# STM32F417_module.net
KiCad netlist of a schematic drawn in EAGLE
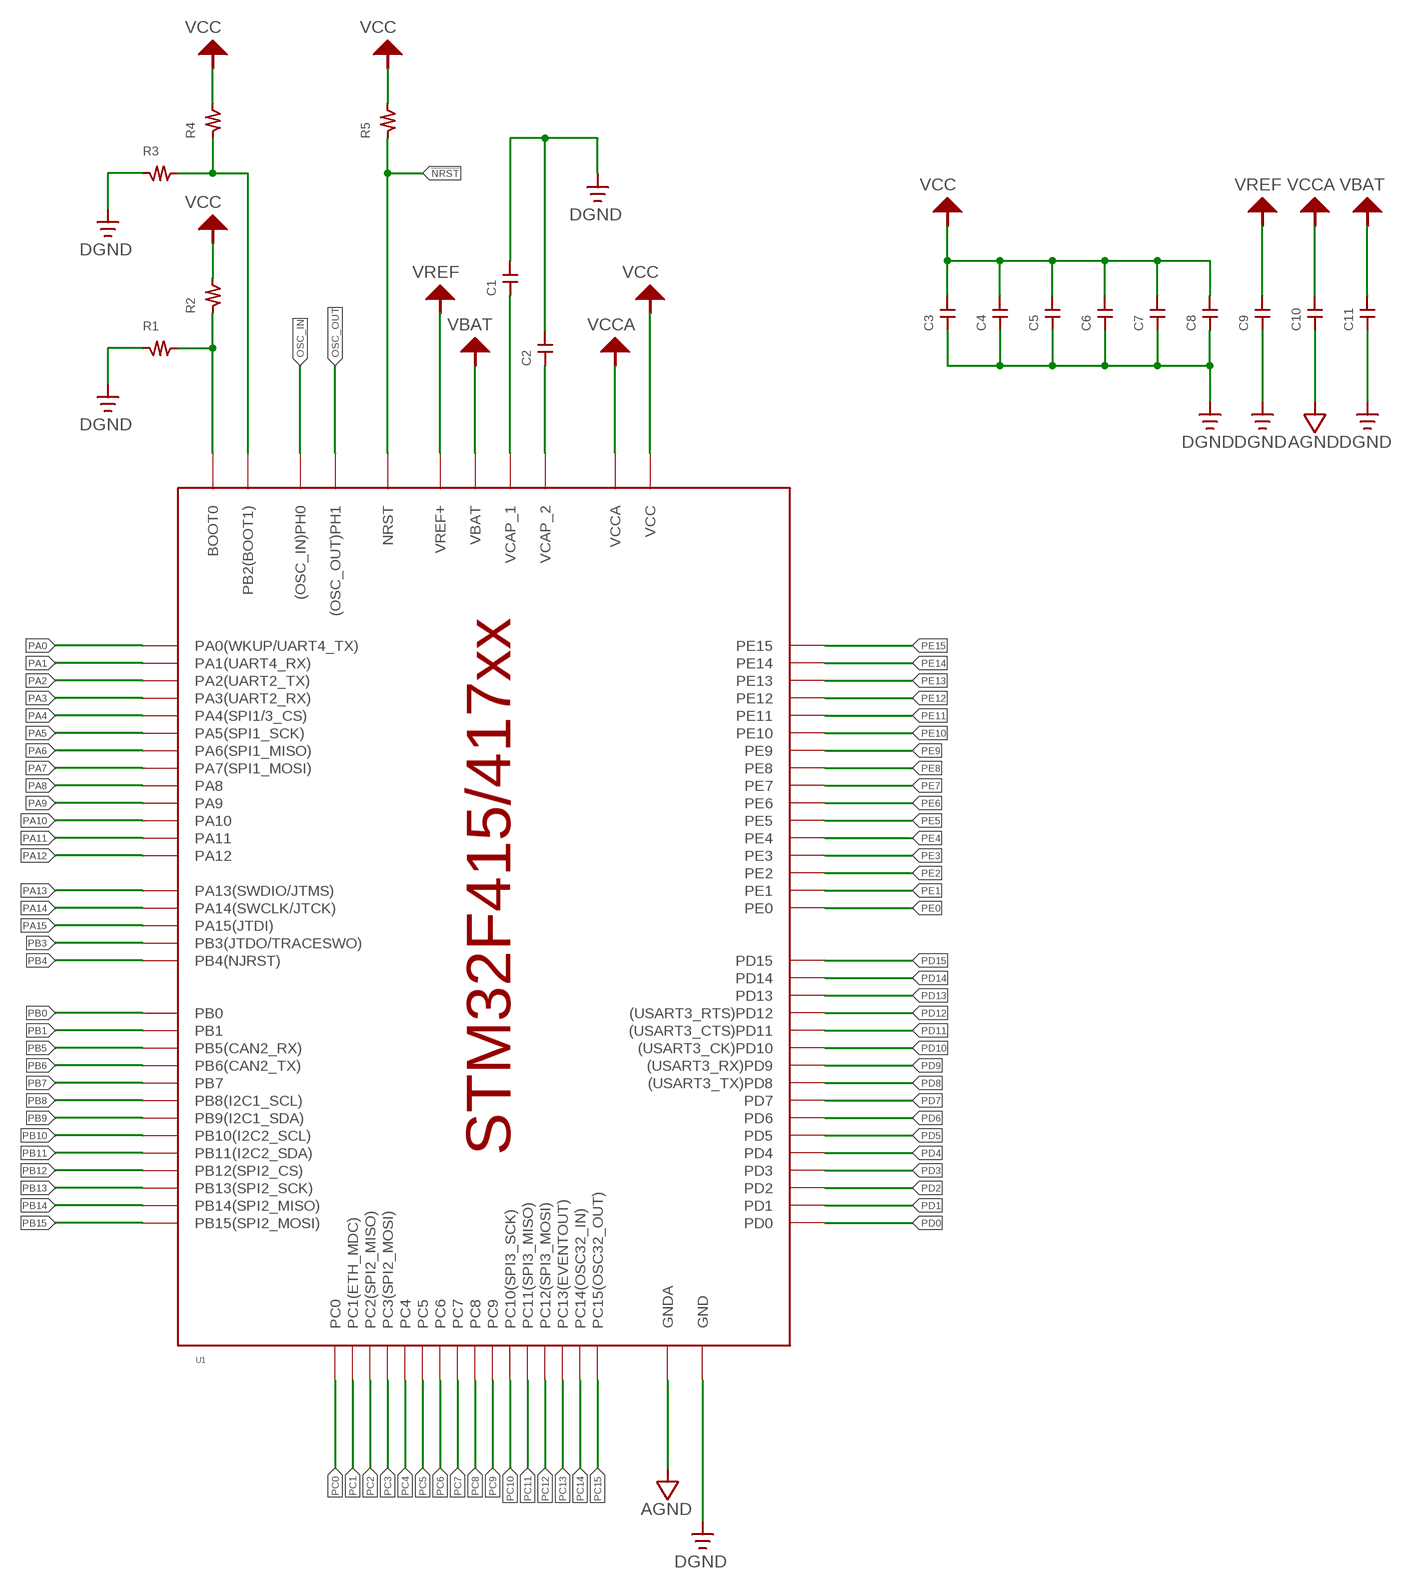
[diagram p0: schematic, sheet 1]

(export (version "E")
  (design (tool "Eeschema 10.0.6"))
  (components
    (comp (ref "C1")
      (value "CAPACITOR_CHIP2012")
      (footprint "eagle-import:2012")
      (libsource (lib "eagle-import") (part "CAPACITOR_CHIP2012"))
    )
    (comp (ref "C2")
      (value "CAPACITOR_CHIP2012")
      (footprint "eagle-import:2012")
      (libsource (lib "eagle-import") (part "CAPACITOR_CHIP2012"))
    )
    (comp (ref "C3")
      (value "CAPACITOR_CHIP2012")
      (footprint "eagle-import:2012")
      (libsource (lib "eagle-import") (part "CAPACITOR_CHIP2012"))
    )
    (comp (ref "C4")
      (value "CAPACITOR_CHIP2012")
      (footprint "eagle-import:2012")
      (libsource (lib "eagle-import") (part "CAPACITOR_CHIP2012"))
    )
    (comp (ref "C5")
      (value "CAPACITOR_CHIP2012")
      (footprint "eagle-import:2012")
      (libsource (lib "eagle-import") (part "CAPACITOR_CHIP2012"))
    )
    (comp (ref "C6")
      (value "CAPACITOR_CHIP2012")
      (footprint "eagle-import:2012")
      (libsource (lib "eagle-import") (part "CAPACITOR_CHIP2012"))
    )
    (comp (ref "C7")
      (value "CAPACITOR_CHIP2012")
      (footprint "eagle-import:2012")
      (libsource (lib "eagle-import") (part "CAPACITOR_CHIP2012"))
    )
    (comp (ref "C8")
      (value "CAPACITOR_CHIP2012")
      (footprint "eagle-import:2012")
      (libsource (lib "eagle-import") (part "CAPACITOR_CHIP2012"))
    )
    (comp (ref "C9")
      (value "CAPACITOR_CHIP2012")
      (footprint "eagle-import:2012")
      (libsource (lib "eagle-import") (part "CAPACITOR_CHIP2012"))
    )
    (comp (ref "C10")
      (value "CAPACITOR_CHIP2012")
      (footprint "eagle-import:2012")
      (libsource (lib "eagle-import") (part "CAPACITOR_CHIP2012"))
    )
    (comp (ref "C11")
      (value "CAPACITOR_CHIP2012")
      (footprint "eagle-import:2012")
      (libsource (lib "eagle-import") (part "CAPACITOR_CHIP2012"))
    )
    (comp (ref "R1")
      (value "RESISTOR_CHIP_2012")
      (footprint "eagle-import:2012")
      (libsource (lib "eagle-import") (part "RESISTOR_CHIP_2012"))
    )
    (comp (ref "R2")
      (value "RESISTOR_CHIP_2012")
      (footprint "eagle-import:2012")
      (libsource (lib "eagle-import") (part "RESISTOR_CHIP_2012"))
    )
    (comp (ref "R3")
      (value "RESISTOR_CHIP_2012")
      (footprint "eagle-import:2012")
      (libsource (lib "eagle-import") (part "RESISTOR_CHIP_2012"))
    )
    (comp (ref "R4")
      (value "RESISTOR_CHIP_2012")
      (footprint "eagle-import:2012")
      (libsource (lib "eagle-import") (part "RESISTOR_CHIP_2012"))
    )
    (comp (ref "R5")
      (value "RESISTOR_CHIP_2012")
      (footprint "eagle-import:2012")
      (libsource (lib "eagle-import") (part "RESISTOR_CHIP_2012"))
    )
    (comp (ref "U1")
      (value "STM32F415/417")
      (footprint "eagle-import:LQFP100")
      (libsource (lib "eagle-import") (part "STM32F415/417"))
    )
  )
  (nets
    (net (code "1") (name "/~{NRST}") (class "Default")
      (node (ref "R5") (pin "P$1") (pinfunction "P$1_P$1") (pintype "passive"))
      (node (ref "U1") (pin "P$14") (pinfunction "NRST_P$14") (pintype "bidirectional"))
    )
    (net (code "2") (name "AGND") (class "Default")
      (node (ref "C10") (pin "P$1") (pinfunction "P$1_P$1") (pintype "passive"))
      (node (ref "U1") (pin "P$20") (pinfunction "GNDA_P$20") (pintype "power_in"))
    )
    (net (code "3") (name "DGND") (class "Default")
      (node (ref "C1") (pin "P$2") (pinfunction "P$2_P$2") (pintype "passive"))
      (node (ref "C11") (pin "P$1") (pinfunction "P$1_P$1") (pintype "passive"))
      (node (ref "C2") (pin "P$2") (pinfunction "P$2_P$2") (pintype "passive"))
      (node (ref "C3") (pin "P$1") (pinfunction "P$1_P$1") (pintype "passive"))
      (node (ref "C4") (pin "P$1") (pinfunction "P$1_P$1") (pintype "passive"))
      (node (ref "C5") (pin "P$1") (pinfunction "P$1_P$1") (pintype "passive"))
      (node (ref "C6") (pin "P$1") (pinfunction "P$1_P$1") (pintype "passive"))
      (node (ref "C7") (pin "P$1") (pinfunction "P$1_P$1") (pintype "passive"))
      (node (ref "C8") (pin "P$1") (pinfunction "P$1_P$1") (pintype "passive"))
      (node (ref "C9") (pin "P$1") (pinfunction "P$1_P$1") (pintype "passive"))
      (node (ref "R1") (pin "P$1") (pinfunction "P$1_P$1") (pintype "passive"))
      (node (ref "R3") (pin "P$1") (pinfunction "P$1_P$1") (pintype "passive"))
      (node (ref "U1") (pin "P$10") (pinfunction "GND_P$10") (pintype "power_in"))
      (node (ref "U1") (pin "P$27") (pinfunction "GND_P$27") (pintype "power_in"))
      (node (ref "U1") (pin "P$74") (pinfunction "GND_P$74") (pintype "power_in"))
      (node (ref "U1") (pin "P$99") (pinfunction "GND_P$99") (pintype "power_in"))
    )
    (net (code "4") (name "Net-(U1-BOOT0)") (class "Default")
      (node (ref "R1") (pin "P$2") (pinfunction "P$2_P$2") (pintype "passive"))
      (node (ref "R2") (pin "P$1") (pinfunction "P$1_P$1") (pintype "passive"))
      (node (ref "U1") (pin "P$94") (pinfunction "BOOT0_P$94") (pintype "bidirectional"))
    )
    (net (code "5") (name "Net-(U1-PB2(BOOT1))") (class "Default")
      (node (ref "R3") (pin "P$2") (pinfunction "P$2_P$2") (pintype "passive"))
      (node (ref "R4") (pin "P$1") (pinfunction "P$1_P$1") (pintype "passive"))
      (node (ref "U1") (pin "P$37") (pinfunction "PB2(BOOT1)_P$37") (pintype "bidirectional"))
    )
    (net (code "6") (name "Net-(U1-VCAP_1)") (class "Default")
      (node (ref "C1") (pin "P$1") (pinfunction "P$1_P$1") (pintype "passive"))
      (node (ref "U1") (pin "P$49") (pinfunction "VCAP_1_P$49") (pintype "power_in"))
    )
    (net (code "7") (name "Net-(U1-VCAP_2)") (class "Default")
      (node (ref "C2") (pin "P$1") (pinfunction "P$1_P$1") (pintype "passive"))
      (node (ref "U1") (pin "P$73") (pinfunction "VCAP_2_P$73") (pintype "power_in"))
    )
    (net (code "8") (name "OSC_IN") (class "Default")
      (node (ref "U1") (pin "P$12") (pinfunction "(OSC_IN)PH0_P$12") (pintype "bidirectional"))
    )
    (net (code "9") (name "OSC_OUT") (class "Default")
      (node (ref "U1") (pin "P$13") (pinfunction "(OSC_OUT)PH1_P$13") (pintype "bidirectional"))
    )
    (net (code "10") (name "PA0") (class "Default")
      (node (ref "U1") (pin "P$23") (pinfunction "PA0(WKUP/UART4_TX)_P$23") (pintype "bidirectional"))
    )
    (net (code "11") (name "PA1") (class "Default")
      (node (ref "U1") (pin "P$24") (pinfunction "PA1(UART4_RX)_P$24") (pintype "bidirectional"))
    )
    (net (code "12") (name "PA2") (class "Default")
      (node (ref "U1") (pin "P$25") (pinfunction "PA2(UART2_TX)_P$25") (pintype "bidirectional"))
    )
    (net (code "13") (name "PA3") (class "Default")
      (node (ref "U1") (pin "P$26") (pinfunction "PA3(UART2_RX)_P$26") (pintype "bidirectional"))
    )
    (net (code "14") (name "PA4") (class "Default")
      (node (ref "U1") (pin "P$29") (pinfunction "PA4(SPI1/3_CS)_P$29") (pintype "bidirectional"))
    )
    (net (code "15") (name "PA5") (class "Default")
      (node (ref "U1") (pin "P$30") (pinfunction "PA5(SPI1_SCK)_P$30") (pintype "bidirectional"))
    )
    (net (code "16") (name "PA6") (class "Default")
      (node (ref "U1") (pin "P$31") (pinfunction "PA6(SPI1_MISO)_P$31") (pintype "bidirectional"))
    )
    (net (code "17") (name "PA7") (class "Default")
      (node (ref "U1") (pin "P$32") (pinfunction "PA7(SPI1_MOSI)_P$32") (pintype "bidirectional"))
    )
    (net (code "18") (name "PA8") (class "Default")
      (node (ref "U1") (pin "P$67") (pinfunction "PA8_P$67") (pintype "bidirectional"))
    )
    (net (code "19") (name "PA9") (class "Default")
      (node (ref "U1") (pin "P$68") (pinfunction "PA9_P$68") (pintype "bidirectional"))
    )
    (net (code "20") (name "PA10") (class "Default")
      (node (ref "U1") (pin "P$69") (pinfunction "PA10_P$69") (pintype "bidirectional"))
    )
    (net (code "21") (name "PA11") (class "Default")
      (node (ref "U1") (pin "P$70") (pinfunction "PA11_P$70") (pintype "bidirectional"))
    )
    (net (code "22") (name "PA12") (class "Default")
      (node (ref "U1") (pin "P$71") (pinfunction "PA12_P$71") (pintype "bidirectional"))
    )
    (net (code "23") (name "PA13") (class "Default")
      (node (ref "U1") (pin "P$72") (pinfunction "PA13(SWDIO/JTMS)_P$72") (pintype "bidirectional"))
    )
    (net (code "24") (name "PA14") (class "Default")
      (node (ref "U1") (pin "P$76") (pinfunction "PA14(SWCLK/JTCK)_P$76") (pintype "bidirectional"))
    )
    (net (code "25") (name "PA15") (class "Default")
      (node (ref "U1") (pin "P$77") (pinfunction "PA15(JTDI)_P$77") (pintype "bidirectional"))
    )
    (net (code "26") (name "PB0") (class "Default")
      (node (ref "U1") (pin "P$35") (pinfunction "PB0_P$35") (pintype "bidirectional"))
    )
    (net (code "27") (name "PB1") (class "Default")
      (node (ref "U1") (pin "P$36") (pinfunction "PB1_P$36") (pintype "bidirectional"))
    )
    (net (code "28") (name "PB3") (class "Default")
      (node (ref "U1") (pin "P$89") (pinfunction "PB3(JTDO/TRACESWO)_P$89") (pintype "bidirectional"))
    )
    (net (code "29") (name "PB4") (class "Default")
      (node (ref "U1") (pin "P$90") (pinfunction "PB4(NJRST)_P$90") (pintype "bidirectional"))
    )
    (net (code "30") (name "PB5") (class "Default")
      (node (ref "U1") (pin "P$91") (pinfunction "PB5(CAN2_RX)_P$91") (pintype "bidirectional"))
    )
    (net (code "31") (name "PB6") (class "Default")
      (node (ref "U1") (pin "P$92") (pinfunction "PB6(CAN2_TX)_P$92") (pintype "bidirectional"))
    )
    (net (code "32") (name "PB7") (class "Default")
      (node (ref "U1") (pin "P$93") (pinfunction "PB7_P$93") (pintype "bidirectional"))
    )
    (net (code "33") (name "PB8") (class "Default")
      (node (ref "U1") (pin "P$95") (pinfunction "PB8(I2C1_SCL)_P$95") (pintype "bidirectional"))
    )
    (net (code "34") (name "PB9") (class "Default")
      (node (ref "U1") (pin "P$96") (pinfunction "PB9(I2C1_SDA)_P$96") (pintype "bidirectional"))
    )
    (net (code "35") (name "PB10") (class "Default")
      (node (ref "U1") (pin "P$47") (pinfunction "PB10(I2C2_SCL)_P$47") (pintype "bidirectional"))
    )
    (net (code "36") (name "PB11") (class "Default")
      (node (ref "U1") (pin "P$48") (pinfunction "PB11(I2C2_SDA)_P$48") (pintype "bidirectional"))
    )
    (net (code "37") (name "PB12") (class "Default")
      (node (ref "U1") (pin "P$51") (pinfunction "PB12(SPI2_CS)_P$51") (pintype "bidirectional"))
    )
    (net (code "38") (name "PB13") (class "Default")
      (node (ref "U1") (pin "P$52") (pinfunction "PB13(SPI2_SCK)_P$52") (pintype "bidirectional"))
    )
    (net (code "39") (name "PB14") (class "Default")
      (node (ref "U1") (pin "P$53") (pinfunction "PB14(SPI2_MISO)_P$53") (pintype "bidirectional"))
    )
    (net (code "40") (name "PB15") (class "Default")
      (node (ref "U1") (pin "P$54") (pinfunction "PB15(SPI2_MOSI)_P$54") (pintype "bidirectional"))
    )
    (net (code "41") (name "PC0") (class "Default")
      (node (ref "U1") (pin "P$15") (pinfunction "PC0_P$15") (pintype "bidirectional"))
    )
    (net (code "42") (name "PC1") (class "Default")
      (node (ref "U1") (pin "P$16") (pinfunction "PC1(ETH_MDC)_P$16") (pintype "bidirectional"))
    )
    (net (code "43") (name "PC2") (class "Default")
      (node (ref "U1") (pin "P$17") (pinfunction "PC2(SPI2_MISO)_P$17") (pintype "bidirectional"))
    )
    (net (code "44") (name "PC3") (class "Default")
      (node (ref "U1") (pin "P$18") (pinfunction "PC3(SPI2_MOSI)_P$18") (pintype "bidirectional"))
    )
    (net (code "45") (name "PC4") (class "Default")
      (node (ref "U1") (pin "P$33") (pinfunction "PC4_P$33") (pintype "bidirectional"))
    )
    (net (code "46") (name "PC5") (class "Default")
      (node (ref "U1") (pin "P$34") (pinfunction "PC5_P$34") (pintype "bidirectional"))
    )
    (net (code "47") (name "PC6") (class "Default")
      (node (ref "U1") (pin "P$63") (pinfunction "PC6_P$63") (pintype "bidirectional"))
    )
    (net (code "48") (name "PC7") (class "Default")
      (node (ref "U1") (pin "P$64") (pinfunction "PC7_P$64") (pintype "bidirectional"))
    )
    (net (code "49") (name "PC8") (class "Default")
      (node (ref "U1") (pin "P$65") (pinfunction "PC8_P$65") (pintype "bidirectional"))
    )
    (net (code "50") (name "PC9") (class "Default")
      (node (ref "U1") (pin "P$66") (pinfunction "PC9_P$66") (pintype "bidirectional"))
    )
    (net (code "51") (name "PC10") (class "Default")
      (node (ref "U1") (pin "P$78") (pinfunction "PC10(SPI3_SCK)_P$78") (pintype "bidirectional"))
    )
    (net (code "52") (name "PC11") (class "Default")
      (node (ref "U1") (pin "P$79") (pinfunction "PC11(SPI3_MISO)_P$79") (pintype "bidirectional"))
    )
    (net (code "53") (name "PC12") (class "Default")
      (node (ref "U1") (pin "P$80") (pinfunction "PC12(SPI3_MOSI)_P$80") (pintype "bidirectional"))
    )
    (net (code "54") (name "PC13") (class "Default")
      (node (ref "U1") (pin "P$7") (pinfunction "PC13(EVENTOUT)_P$7") (pintype "bidirectional"))
    )
    (net (code "55") (name "PC14") (class "Default")
      (node (ref "U1") (pin "P$8") (pinfunction "PC14(OSC32_IN)_P$8") (pintype "bidirectional"))
    )
    (net (code "56") (name "PC15") (class "Default")
      (node (ref "U1") (pin "P$9") (pinfunction "PC15(OSC32_OUT)_P$9") (pintype "bidirectional"))
    )
    (net (code "57") (name "PD0") (class "Default")
      (node (ref "U1") (pin "P$81") (pinfunction "PD0_P$81") (pintype "bidirectional"))
    )
    (net (code "58") (name "PD1") (class "Default")
      (node (ref "U1") (pin "P$82") (pinfunction "PD1_P$82") (pintype "bidirectional"))
    )
    (net (code "59") (name "PD2") (class "Default")
      (node (ref "U1") (pin "P$83") (pinfunction "PD2_P$83") (pintype "bidirectional"))
    )
    (net (code "60") (name "PD3") (class "Default")
      (node (ref "U1") (pin "P$84") (pinfunction "PD3_P$84") (pintype "bidirectional"))
    )
    (net (code "61") (name "PD4") (class "Default")
      (node (ref "U1") (pin "P$85") (pinfunction "PD4_P$85") (pintype "bidirectional"))
    )
    (net (code "62") (name "PD5") (class "Default")
      (node (ref "U1") (pin "P$86") (pinfunction "PD5_P$86") (pintype "bidirectional"))
    )
    (net (code "63") (name "PD6") (class "Default")
      (node (ref "U1") (pin "P$87") (pinfunction "PD6_P$87") (pintype "bidirectional"))
    )
    (net (code "64") (name "PD7") (class "Default")
      (node (ref "U1") (pin "P$88") (pinfunction "PD7_P$88") (pintype "bidirectional"))
    )
    (net (code "65") (name "PD8") (class "Default")
      (node (ref "U1") (pin "P$55") (pinfunction "(USART3_TX)PD8_P$55") (pintype "bidirectional"))
    )
    (net (code "66") (name "PD9") (class "Default")
      (node (ref "U1") (pin "P$56") (pinfunction "(USART3_RX)PD9_P$56") (pintype "bidirectional"))
    )
    (net (code "67") (name "PD10") (class "Default")
      (node (ref "U1") (pin "P$57") (pinfunction "(USART3_CK)PD10_P$57") (pintype "bidirectional"))
    )
    (net (code "68") (name "PD11") (class "Default")
      (node (ref "U1") (pin "P$58") (pinfunction "(USART3_CTS)PD11_P$58") (pintype "bidirectional"))
    )
    (net (code "69") (name "PD12") (class "Default")
      (node (ref "U1") (pin "P$59") (pinfunction "(USART3_RTS)PD12_P$59") (pintype "bidirectional"))
    )
    (net (code "70") (name "PD13") (class "Default")
      (node (ref "U1") (pin "P$60") (pinfunction "PD13_P$60") (pintype "bidirectional"))
    )
    (net (code "71") (name "PD14") (class "Default")
      (node (ref "U1") (pin "P$61") (pinfunction "PD14_P$61") (pintype "bidirectional"))
    )
    (net (code "72") (name "PD15") (class "Default")
      (node (ref "U1") (pin "P$62") (pinfunction "PD15_P$62") (pintype "bidirectional"))
    )
    (net (code "73") (name "PE0") (class "Default")
      (node (ref "U1") (pin "P$97") (pinfunction "PE0_P$97") (pintype "bidirectional"))
    )
    (net (code "74") (name "PE1") (class "Default")
      (node (ref "U1") (pin "P$98") (pinfunction "PE1_P$98") (pintype "bidirectional"))
    )
    (net (code "75") (name "PE2") (class "Default")
      (node (ref "U1") (pin "P$1") (pinfunction "PE2_P$1") (pintype "bidirectional"))
    )
    (net (code "76") (name "PE3") (class "Default")
      (node (ref "U1") (pin "P$2") (pinfunction "PE3_P$2") (pintype "bidirectional"))
    )
    (net (code "77") (name "PE4") (class "Default")
      (node (ref "U1") (pin "P$3") (pinfunction "PE4_P$3") (pintype "bidirectional"))
    )
    (net (code "78") (name "PE5") (class "Default")
      (node (ref "U1") (pin "P$4") (pinfunction "PE5_P$4") (pintype "bidirectional"))
    )
    (net (code "79") (name "PE6") (class "Default")
      (node (ref "U1") (pin "P$5") (pinfunction "PE6_P$5") (pintype "bidirectional"))
    )
    (net (code "80") (name "PE7") (class "Default")
      (node (ref "U1") (pin "P$38") (pinfunction "PE7_P$38") (pintype "bidirectional"))
    )
    (net (code "81") (name "PE8") (class "Default")
      (node (ref "U1") (pin "P$39") (pinfunction "PE8_P$39") (pintype "bidirectional"))
    )
    (net (code "82") (name "PE9") (class "Default")
      (node (ref "U1") (pin "P$40") (pinfunction "PE9_P$40") (pintype "bidirectional"))
    )
    (net (code "83") (name "PE10") (class "Default")
      (node (ref "U1") (pin "P$41") (pinfunction "PE10_P$41") (pintype "bidirectional"))
    )
    (net (code "84") (name "PE11") (class "Default")
      (node (ref "U1") (pin "P$42") (pinfunction "PE11_P$42") (pintype "bidirectional"))
    )
    (net (code "85") (name "PE12") (class "Default")
      (node (ref "U1") (pin "P$43") (pinfunction "PE12_P$43") (pintype "bidirectional"))
    )
    (net (code "86") (name "PE13") (class "Default")
      (node (ref "U1") (pin "P$44") (pinfunction "PE13_P$44") (pintype "bidirectional"))
    )
    (net (code "87") (name "PE14") (class "Default")
      (node (ref "U1") (pin "P$45") (pinfunction "PE14_P$45") (pintype "bidirectional"))
    )
    (net (code "88") (name "PE15") (class "Default")
      (node (ref "U1") (pin "P$46") (pinfunction "PE15_P$46") (pintype "bidirectional"))
    )
    (net (code "89") (name "VBAT") (class "Default")
      (node (ref "C11") (pin "P$2") (pinfunction "P$2_P$2") (pintype "passive"))
      (node (ref "U1") (pin "P$6") (pinfunction "VBAT_P$6") (pintype "power_in"))
    )
    (net (code "90") (name "VCC") (class "Default")
      (node (ref "C3") (pin "P$2") (pinfunction "P$2_P$2") (pintype "passive"))
      (node (ref "C4") (pin "P$2") (pinfunction "P$2_P$2") (pintype "passive"))
      (node (ref "C5") (pin "P$2") (pinfunction "P$2_P$2") (pintype "passive"))
      (node (ref "C6") (pin "P$2") (pinfunction "P$2_P$2") (pintype "passive"))
      (node (ref "C7") (pin "P$2") (pinfunction "P$2_P$2") (pintype "passive"))
      (node (ref "C8") (pin "P$2") (pinfunction "P$2_P$2") (pintype "passive"))
      (node (ref "R2") (pin "P$2") (pinfunction "P$2_P$2") (pintype "passive"))
      (node (ref "R4") (pin "P$2") (pinfunction "P$2_P$2") (pintype "passive"))
      (node (ref "R5") (pin "P$2") (pinfunction "P$2_P$2") (pintype "passive"))
      (node (ref "U1") (pin "P$100") (pinfunction "VCC_P$100") (pintype "power_in"))
      (node (ref "U1") (pin "P$11") (pinfunction "VCC_P$11") (pintype "power_in"))
      (node (ref "U1") (pin "P$19") (pinfunction "VCC_P$19") (pintype "power_in"))
      (node (ref "U1") (pin "P$28") (pinfunction "VCC_P$28") (pintype "power_in"))
      (node (ref "U1") (pin "P$50") (pinfunction "VCC_P$50") (pintype "power_in"))
      (node (ref "U1") (pin "P$75") (pinfunction "VCC_P$75") (pintype "power_in"))
    )
    (net (code "91") (name "VCCA") (class "Default")
      (node (ref "C10") (pin "P$2") (pinfunction "P$2_P$2") (pintype "passive"))
      (node (ref "U1") (pin "P$22") (pinfunction "VCCA_P$22") (pintype "power_in"))
    )
    (net (code "92") (name "VREF") (class "Default")
      (node (ref "C9") (pin "P$2") (pinfunction "P$2_P$2") (pintype "passive"))
      (node (ref "U1") (pin "P$21") (pinfunction "VREF+_P$21") (pintype "power_in"))
    )
  )
)
